# Power.net
KiCad netlist of a schematic drawn in Altium Designer
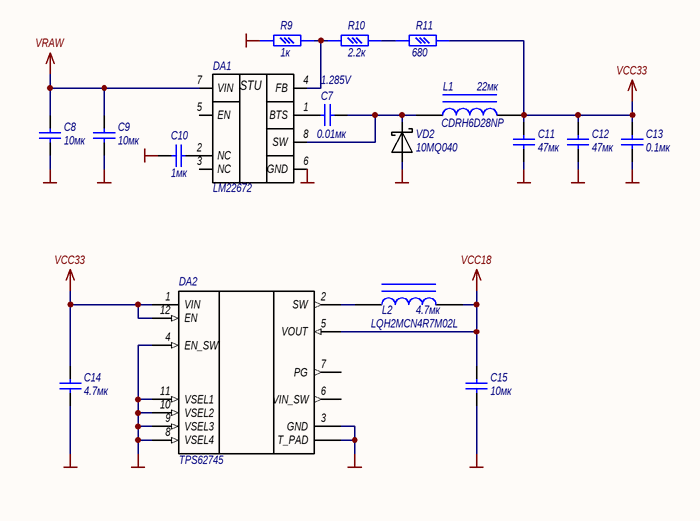
[diagram p0: Power.SchDoc]

(export (version "E")
  (design (tool "Eeschema 10.0.6"))
  (components
    (comp (ref "C7")
      (value "0.01мк")
      (footprint "CAPC3216L")
      (description "Samsung MLCC Capacitor")
      (fields
        (field (name "MANUFACTURER") "Samsung")
        (field (name "MANUFACTURERPARTNUMBER") "CL31B103KBCNNN")
        (field (name "PUBLISHER") "Komiss Labs.")
      )
      (libsource (lib "Samsung_MLCC_Capacitors") (part "CL31"))
    )
    (comp (ref "C8")
      (value "10мк")
      (footprint "CAPC3216L")
      (description "Samsung MLCC Capacitor")
      (fields
        (field (name "MANUFACTURER") "Samsung")
        (field (name "MANUFACTURERPARTNUMBER") "CL31A106KBHNNN")
        (field (name "PUBLISHER") "Komiss Labs.")
      )
      (libsource (lib "Samsung_MLCC_Capacitors") (part "CL31"))
    )
    (comp (ref "C9")
      (value "10мк")
      (footprint "CAPC3216L")
      (description "Samsung MLCC Capacitor")
      (fields
        (field (name "MANUFACTURER") "Samsung")
        (field (name "MANUFACTURERPARTNUMBER") "CL31A106KBHNNN")
        (field (name "PUBLISHER") "Komiss Labs.")
      )
      (libsource (lib "Samsung_MLCC_Capacitors") (part "CL31"))
    )
    (comp (ref "C10")
      (value "1мк")
      (footprint "CAPC1608L")
      (description "Samsung MLCC Capacitor")
      (fields
        (field (name "MANUFACTURER") "Samsung")
        (field (name "MANUFACTURERPARTNUMBER") "CL10A105KA5LNN")
        (field (name "PUBLISHER") "Komiss Labs.")
      )
      (libsource (lib "Samsung_MLCC_Capacitors") (part "CL10"))
    )
    (comp (ref "C11")
      (value "47мк")
      (footprint "CAPC3225L")
      (description "Samsung MLCC Capacitor")
      (fields
        (field (name "MANUFACTURER") "Samsung")
        (field (name "MANUFACTURERPARTNUMBER") "CL32A476MQJNNN")
        (field (name "PUBLISHER") "Komiss Labs.")
      )
      (libsource (lib "Samsung_MLCC_Capacitors") (part "CL32"))
    )
    (comp (ref "C12")
      (value "47мк")
      (footprint "CAPC3225L")
      (description "Samsung MLCC Capacitor")
      (fields
        (field (name "MANUFACTURER") "Samsung")
        (field (name "MANUFACTURERPARTNUMBER") "CL32A476MQJNNN")
        (field (name "PUBLISHER") "Komiss Labs.")
      )
      (libsource (lib "Samsung_MLCC_Capacitors") (part "CL32"))
    )
    (comp (ref "C13")
      (value "0.1мк")
      (footprint "CAPC3216L")
      (description "Samsung MLCC Capacitor")
      (fields
        (field (name "MANUFACTURER") "Samsung")
        (field (name "MANUFACTURERPARTNUMBER") "CL31B104KACNNN")
        (field (name "PUBLISHER") "Komiss Labs.")
      )
      (libsource (lib "Samsung_MLCC_Capacitors") (part "CL31"))
    )
    (comp (ref "C14")
      (value "4.7мк")
      (footprint "CAPC1005L")
      (description "Samsung MLCC Capacitor")
      (fields
        (field (name "MANUFACTURER") "Samsung")
        (field (name "MANUFACTURERPARTNUMBER") "CL05A475MQ5NRN")
        (field (name "PUBLISHER") "Komiss Labs.")
      )
      (libsource (lib "Samsung_MLCC_Capacitors") (part "CL05"))
    )
    (comp (ref "C15")
      (value "10мк")
      (footprint "CAPC1608L")
      (description "Samsung MLCC Capacitor")
      (fields
        (field (name "MANUFACTURER") "Samsung")
        (field (name "MANUFACTURERPARTNUMBER") "CL10A106MO8NQN")
        (field (name "PUBLISHER") "Komiss Labs.")
      )
      (libsource (lib "Samsung_MLCC_Capacitors") (part "CL10"))
    )
    (comp (ref "DA1")
      (value "LM22672")
      (footprint "MRA08B_N")
      (description "40 V, 0.5A Simple Switcher, Step-Down")
      (fields (field (name "MANUFACTURER") "Texas Instruments"))
      (libsource (lib "Komiss") (part "LM2674MX-XXX"))
    )
    (comp (ref "DA2")
      (value "TPS62745")
      (footprint "WSON-12")
      (description "Dual-cell Ultra Low IQ Step Down Converter for Low Power Wireless  Applications")
      (fields (field (name "MANUFACTURER") "Texas Instruments"))
      (libsource (lib "MySchLib") (part "TPS62745"))
    )
    (comp (ref "L1")
      (value "CDRH6D28NP")
      (footprint "CDRH6D38")
      (description "Magnetic-Core Inductor")
      (fields
        (field (name "ALTIUM_VALUE") "22мк")
        (field (name "MANUFACTURER") "Sumida")
        (field (name "MANUFACTURERPARTNUMBER") "CDRH6D28NP-220NC")
        (field (name "PUBLISHER") "Altium Limited")
      )
      (libsource (lib "Miscellaneous Devices") (part "Inductor Iron"))
    )
    (comp (ref "L2")
      (value "LQH2MCN4R7M02L")
      (footprint "INDUCTOR0806")
      (description "Magnetic-Core Inductor")
      (fields
        (field (name "ALTIUM_VALUE") "4.7мк")
        (field (name "MANUFACTURER") "Sumida")
        (field (name "TOLERANCE") "±10%")
        (field (name "PUBLISHER") "Altium Limited")
      )
      (libsource (lib "Miscellaneous Devices") (part "Inductor Iron"))
    )
    (comp (ref "R9")
      (value "1к")
      (footprint "RESC1608L")
      (description "General Thick Film Chip Resistor")
      (fields
        (field (name "TOLERANCE") "±5%")
        (field (name "MANUFACTURER") "Samsung")
        (field (name "PUBLISHER") "Komiss Labs.")
      )
      (libsource (lib "Samsung_Chip_Resistors") (part "RC1608"))
    )
    (comp (ref "R10")
      (value "2.2к")
      (footprint "RESC1608L")
      (description "General Thick Film Chip Resistor")
      (fields
        (field (name "TOLERANCE") "±5%")
        (field (name "MANUFACTURER") "Samsung")
        (field (name "PUBLISHER") "Komiss Labs.")
      )
      (libsource (lib "Samsung_Chip_Resistors") (part "RC1608"))
    )
    (comp (ref "R11")
      (value "680")
      (footprint "RESC1608L")
      (description "General Thick Film Chip Resistor")
      (fields
        (field (name "TOLERANCE") "±5%")
        (field (name "MANUFACTURER") "Samsung")
        (field (name "PUBLISHER") "Komiss Labs.")
      )
      (libsource (lib "Samsung_Chip_Resistors") (part "RC1608"))
    )
    (comp (ref "VD2")
      (value "10MQ040")
      (footprint "SMA_")
      (description "Schottky Barrier Diode")
      (fields (field (name "MANUFACTURER") "International Rectifier"))
      (libsource (lib "DIOD") (part "10MQ040"))
    )
  )
  (nets
    (net (code "1") (name "GND") (class "Default")
      (node (ref "C10") (pin "1") (pinfunction "1_1") (pintype "passive"))
      (node (ref "C11") (pin "1") (pinfunction "1_1") (pintype "passive"))
      (node (ref "C12") (pin "1") (pinfunction "1_1") (pintype "passive"))
      (node (ref "C13") (pin "1") (pinfunction "1_1") (pintype "passive"))
      (node (ref "C14") (pin "1") (pinfunction "1_1") (pintype "passive"))
      (node (ref "C15") (pin "1") (pinfunction "1_1") (pintype "passive"))
      (node (ref "C8") (pin "1") (pinfunction "1_1") (pintype "passive"))
      (node (ref "C9") (pin "1") (pinfunction "1_1") (pintype "passive"))
      (node (ref "DA1") (pin "6") (pinfunction "GND_6") (pintype "passive"))
      (node (ref "DA2") (pin "10") (pinfunction "VSEL2_10") (pintype "input"))
      (node (ref "DA2") (pin "11") (pinfunction "VSEL1_11") (pintype "input"))
      (node (ref "DA2") (pin "13") (pinfunction "T_PAD_13") (pintype "power_in"))
      (node (ref "DA2") (pin "3") (pinfunction "GND_3") (pintype "power_in"))
      (node (ref "DA2") (pin "4") (pinfunction "EN_SW_4") (pintype "input"))
      (node (ref "DA2") (pin "8") (pinfunction "VSEL4_8") (pintype "input"))
      (node (ref "DA2") (pin "9") (pinfunction "VSEL3_9") (pintype "input"))
      (node (ref "R9") (pin "1") (pinfunction "1_1") (pintype "passive"))
      (node (ref "VD2") (pin "1") (pinfunction "1_1") (pintype "passive"))
    )
    (net (code "2") (name "Net-(C10-Pad2)") (class "Default")
      (node (ref "C10") (pin "2") (pinfunction "2_2") (pintype "passive"))
      (node (ref "DA1") (pin "2") (pinfunction "NC_2") (pintype "passive"))
    )
    (net (code "3") (name "Net-(DA1-BTS)") (class "Default")
      (node (ref "C7") (pin "2") (pinfunction "2_2") (pintype "passive"))
      (node (ref "DA1") (pin "1") (pinfunction "BTS_1") (pintype "passive"))
    )
    (net (code "4") (name "Net-(DA1-FB)") (class "Default")
      (node (ref "DA1") (pin "4") (pinfunction "FB_4") (pintype "passive"))
      (node (ref "R10") (pin "1") (pinfunction "1_1") (pintype "passive"))
      (node (ref "R9") (pin "2") (pinfunction "2_2") (pintype "passive"))
    )
    (net (code "5") (name "Net-(DA1-SW)") (class "Default")
      (node (ref "C7") (pin "1") (pinfunction "1_1") (pintype "passive"))
      (node (ref "DA1") (pin "8") (pinfunction "SW_8") (pintype "passive"))
      (node (ref "L1") (pin "1") (pinfunction "1_1") (pintype "passive"))
      (node (ref "VD2") (pin "2") (pinfunction "2_2") (pintype "passive"))
    )
    (net (code "6") (name "Net-(DA2-SW)") (class "Default")
      (node (ref "DA2") (pin "2") (pinfunction "SW_2") (pintype "output"))
      (node (ref "L2") (pin "1") (pinfunction "1_1") (pintype "passive"))
    )
    (net (code "7") (name "Net-(R10-Pad2)") (class "Default")
      (node (ref "R10") (pin "2") (pinfunction "2_2") (pintype "passive"))
      (node (ref "R11") (pin "1") (pinfunction "1_1") (pintype "passive"))
    )
    (net (code "8") (name "VCC18") (class "Default")
      (node (ref "C15") (pin "2") (pinfunction "2_2") (pintype "passive"))
      (node (ref "DA2") (pin "5") (pinfunction "VOUT_5") (pintype "input"))
      (node (ref "L2") (pin "2") (pinfunction "2_2") (pintype "passive"))
    )
    (net (code "9") (name "VCC33") (class "Default")
      (node (ref "C11") (pin "2") (pinfunction "2_2") (pintype "passive"))
      (node (ref "C12") (pin "2") (pinfunction "2_2") (pintype "passive"))
      (node (ref "C13") (pin "2") (pinfunction "2_2") (pintype "passive"))
      (node (ref "C14") (pin "2") (pinfunction "2_2") (pintype "passive"))
      (node (ref "DA2") (pin "1") (pinfunction "VIN_1") (pintype "power_in"))
      (node (ref "DA2") (pin "12") (pinfunction "EN_12") (pintype "input"))
      (node (ref "L1") (pin "2") (pinfunction "2_2") (pintype "passive"))
      (node (ref "R11") (pin "2") (pinfunction "2_2") (pintype "passive"))
    )
    (net (code "10") (name "VRAW") (class "Default")
      (node (ref "C8") (pin "2") (pinfunction "2_2") (pintype "passive"))
      (node (ref "C9") (pin "2") (pinfunction "2_2") (pintype "passive"))
      (node (ref "DA1") (pin "7") (pinfunction "VIN_7") (pintype "passive"))
    )
    (net (code "11") (name "unconnected-(DA1-EN-Pad5)") (class "Default")
      (node (ref "DA1") (pin "5") (pinfunction "EN_5") (pintype "passive"))
    )
    (net (code "12") (name "unconnected-(DA1-NC-Pad3)") (class "Default")
      (node (ref "DA1") (pin "3") (pinfunction "NC_3") (pintype "passive"))
    )
    (net (code "13") (name "unconnected-(DA2-PG-Pad7)") (class "Default")
      (node (ref "DA2") (pin "7") (pinfunction "PG_7") (pintype "output"))
    )
    (net (code "14") (name "unconnected-(DA2-VIN_SW-Pad6)") (class "Default")
      (node (ref "DA2") (pin "6") (pinfunction "VIN_SW_6") (pintype "output"))
    )
  )
)
